# Relay_Driver.net
KiCad netlist of a schematic drawn in Altium Designer
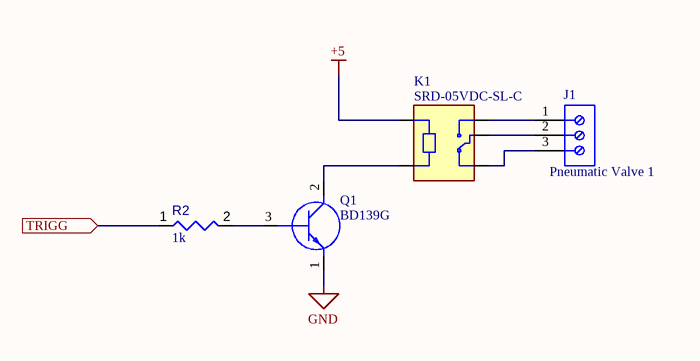
[diagram p0: Relay_Driver.SchDoc]

(export (version "E")
  (design (tool "Eeschema 10.0.6"))
  (components
    (comp (ref "J1")
      (value "Pneumatic Valve 1")
      (footprint "691101710003")
      (fields (field (name "VOLTAGE") "250V"))
      (libsource (lib "Altium Content Vault") (part "TBL - 1R - 03P - Screw"))
    )
    (comp (ref "K1")
      (value "SRD-05VDC-SL-C")
      (footprint "RELAY_SRD-05VDC-SL-C")
      (fields (field (name "MF") "Songle Relay"))
      (libsource (lib "SRD-05VDC-SL-C") (part "SRD-05VDC-SL-C"))
    )
    (comp (ref "Q1")
      (value "BD139G")
      (footprint "SamacSys:TO229P300X760X1364-3P")
      (description "Transistor BJT NPN")
      (fields (field (name "MOUSER PART NUMBER") "863-BD139G"))
      (libsource (lib "*") (part "BD139G"))
    )
    (comp (ref "R2")
      (value "1k")
      (footprint "RESA60-630X240")
      (description "Axial Resistor, 1 KOhm, +/- 1%, 250 mW, -55 to 155 degC, 2-Pin THD, RoHS, Bulk")
      (fields (field (name "TOLERANCE") "1%") (field (name "POWER") "250mW"))
      (libsource (lib "Nidula  Gunawardana") (part "RES-2"))
    )
  )
  (nets
    (net (code "1") (name "+5") (class "Default")
      (node (ref "K1") (pin "A1") (pinfunction "A1_A1") (pintype "passive"))
    )
    (net (code "2") (name "/TRIGG") (class "Default")
      (node (ref "R2") (pin "1") (pinfunction "1_1") (pintype "passive"))
    )
    (net (code "3") (name "GND") (class "Default")
      (node (ref "Q1") (pin "1") (pinfunction "E_1") (pintype "passive"))
    )
    (net (code "4") (name "Net-(J1-Pad1)") (class "Default")
      (node (ref "J1") (pin "1") (pinfunction "1_1") (pintype "passive"))
      (node (ref "K1") (pin "NO") (pinfunction "NO_NO") (pintype "passive"))
    )
    (net (code "5") (name "Net-(J1-Pad2)") (class "Default")
      (node (ref "J1") (pin "2") (pinfunction "2_2") (pintype "passive"))
      (node (ref "K1") (pin "COM") (pinfunction "COM_COM") (pintype "passive"))
    )
    (net (code "6") (name "Net-(J1-Pad3)") (class "Default")
      (node (ref "J1") (pin "3") (pinfunction "3_3") (pintype "passive"))
      (node (ref "K1") (pin "NC") (pinfunction "NC_NC") (pintype "passive"))
    )
    (net (code "7") (name "Net-(Q1-B)") (class "Default")
      (node (ref "Q1") (pin "3") (pinfunction "B_3") (pintype "passive"))
      (node (ref "R2") (pin "2") (pinfunction "2_2") (pintype "passive"))
    )
    (net (code "8") (name "Net-(Q1-C)") (class "Default")
      (node (ref "K1") (pin "A2") (pinfunction "A2_A2") (pintype "passive"))
      (node (ref "Q1") (pin "2") (pinfunction "C_2") (pintype "passive"))
    )
  )
)
